# firefly_xiao.net
KiCad netlist of a schematic drawn in EasyEDA Pro
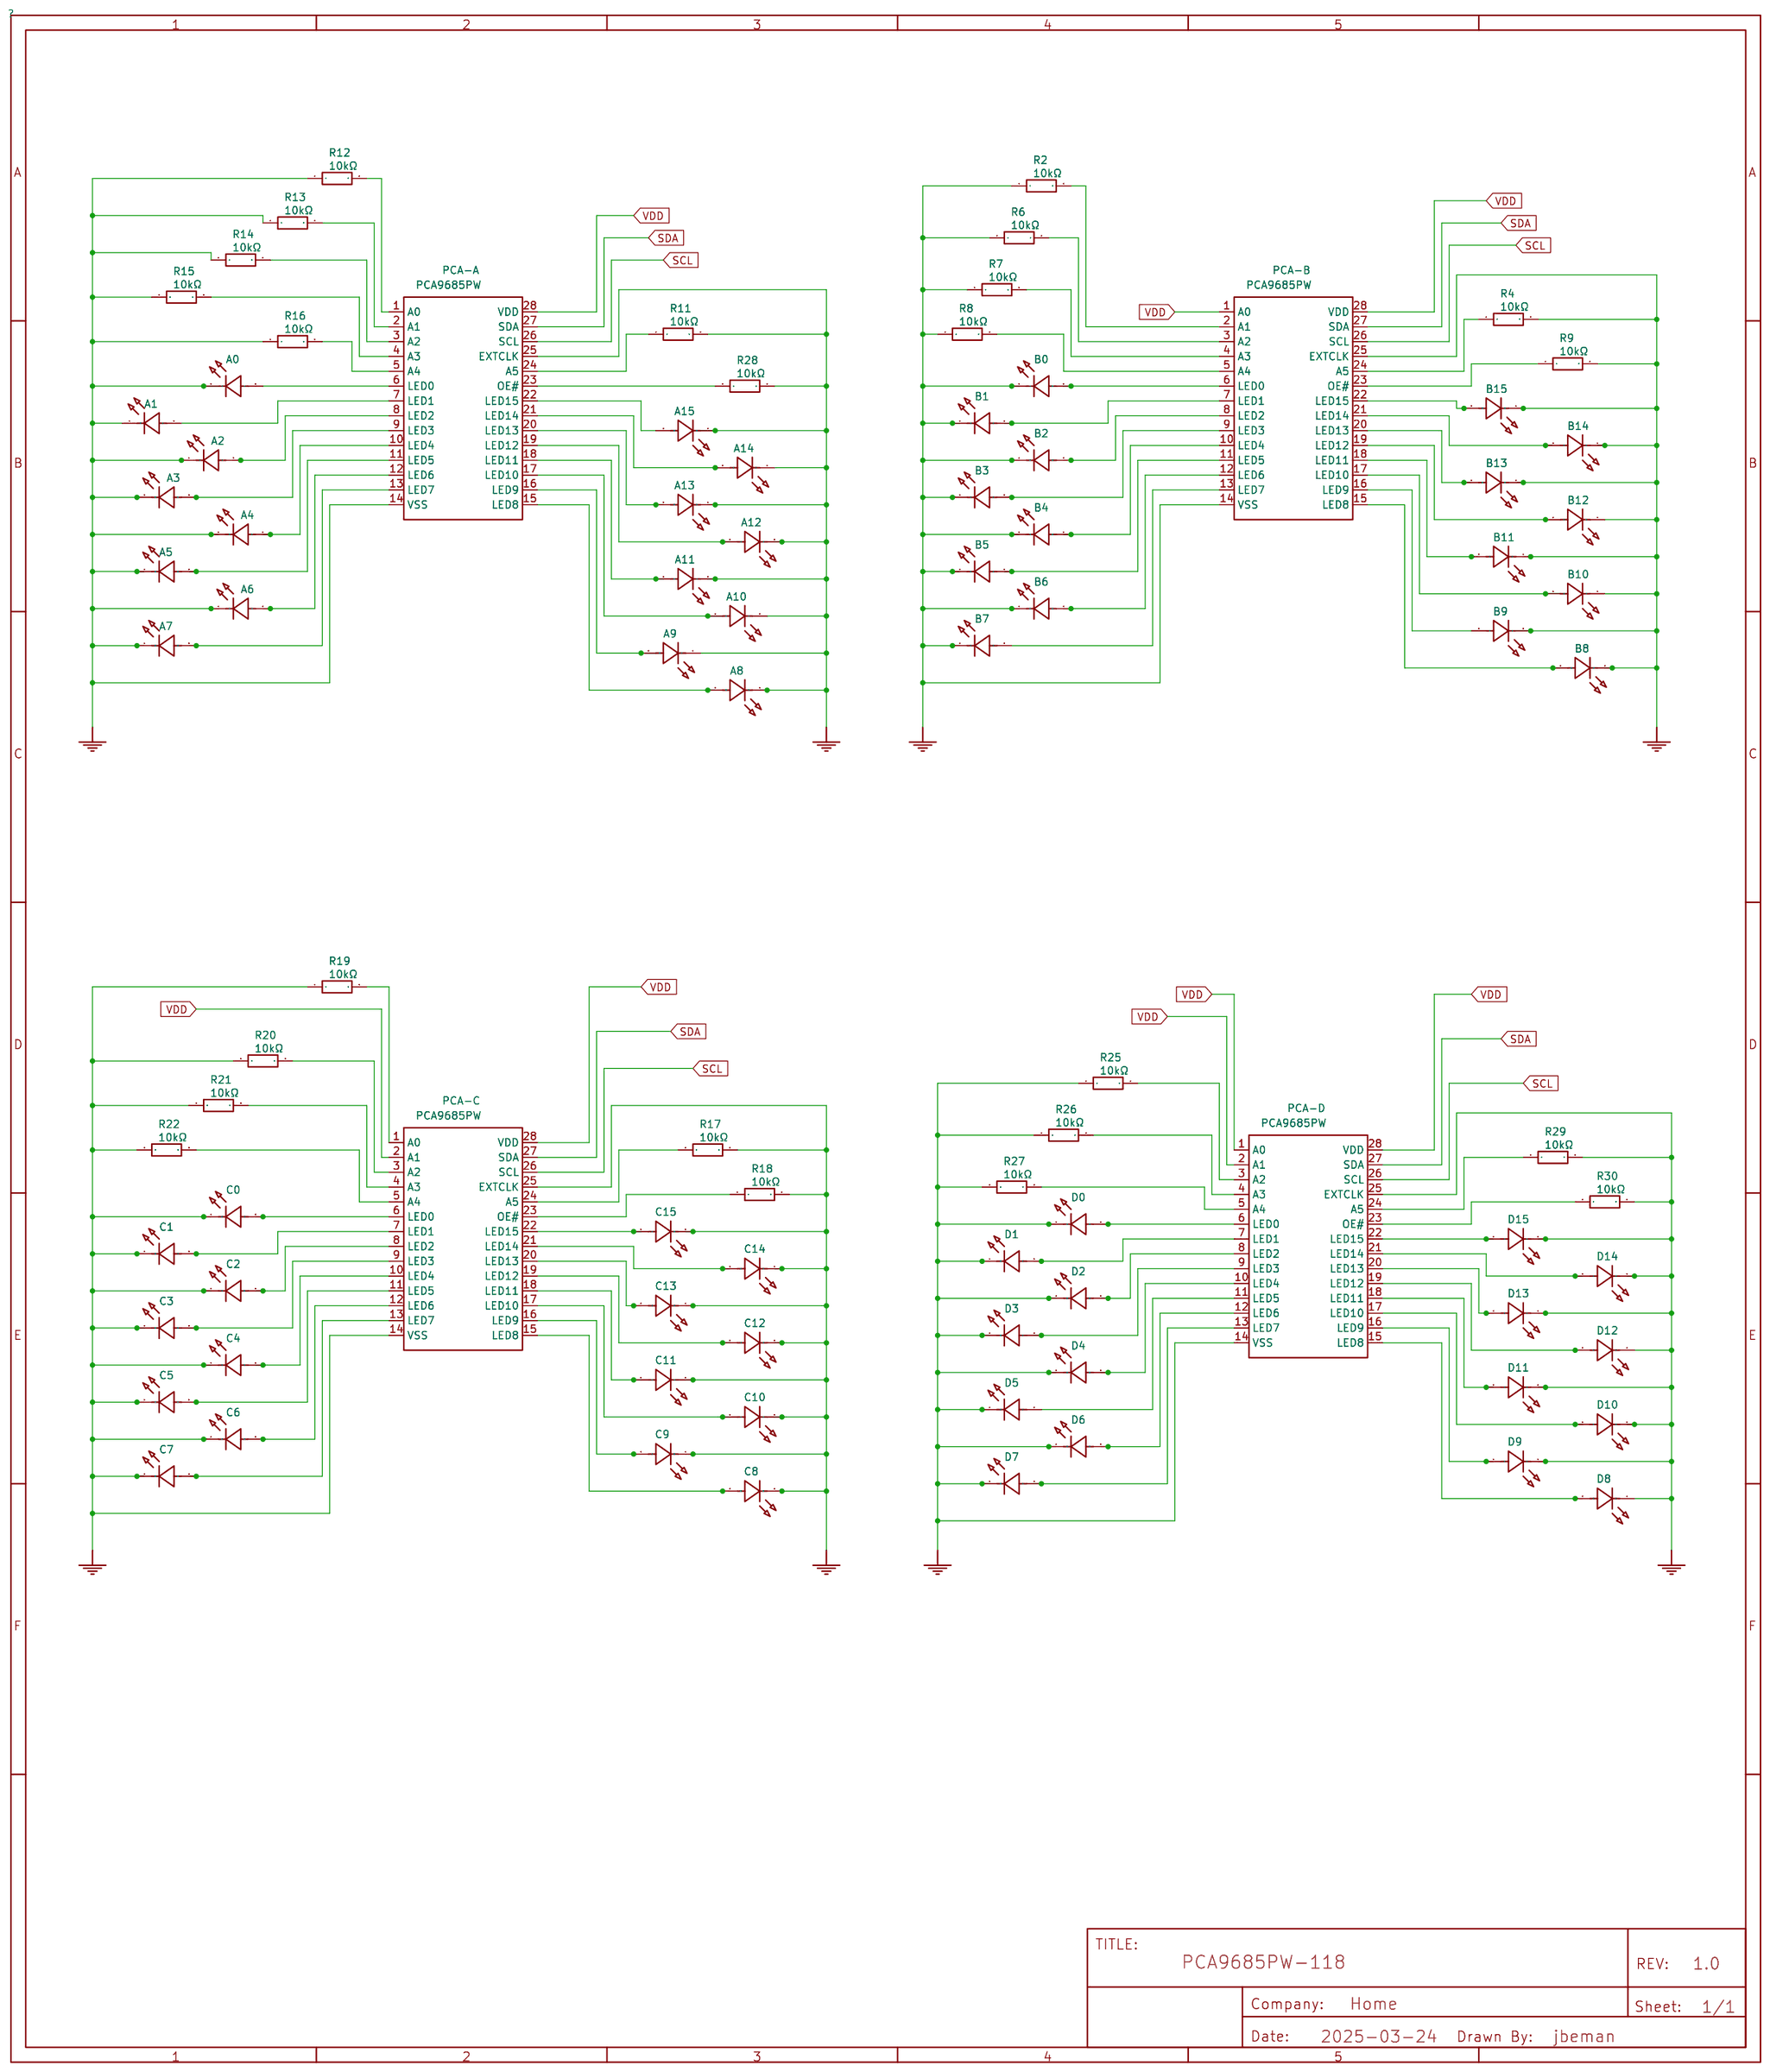
[diagram p0: PCA]
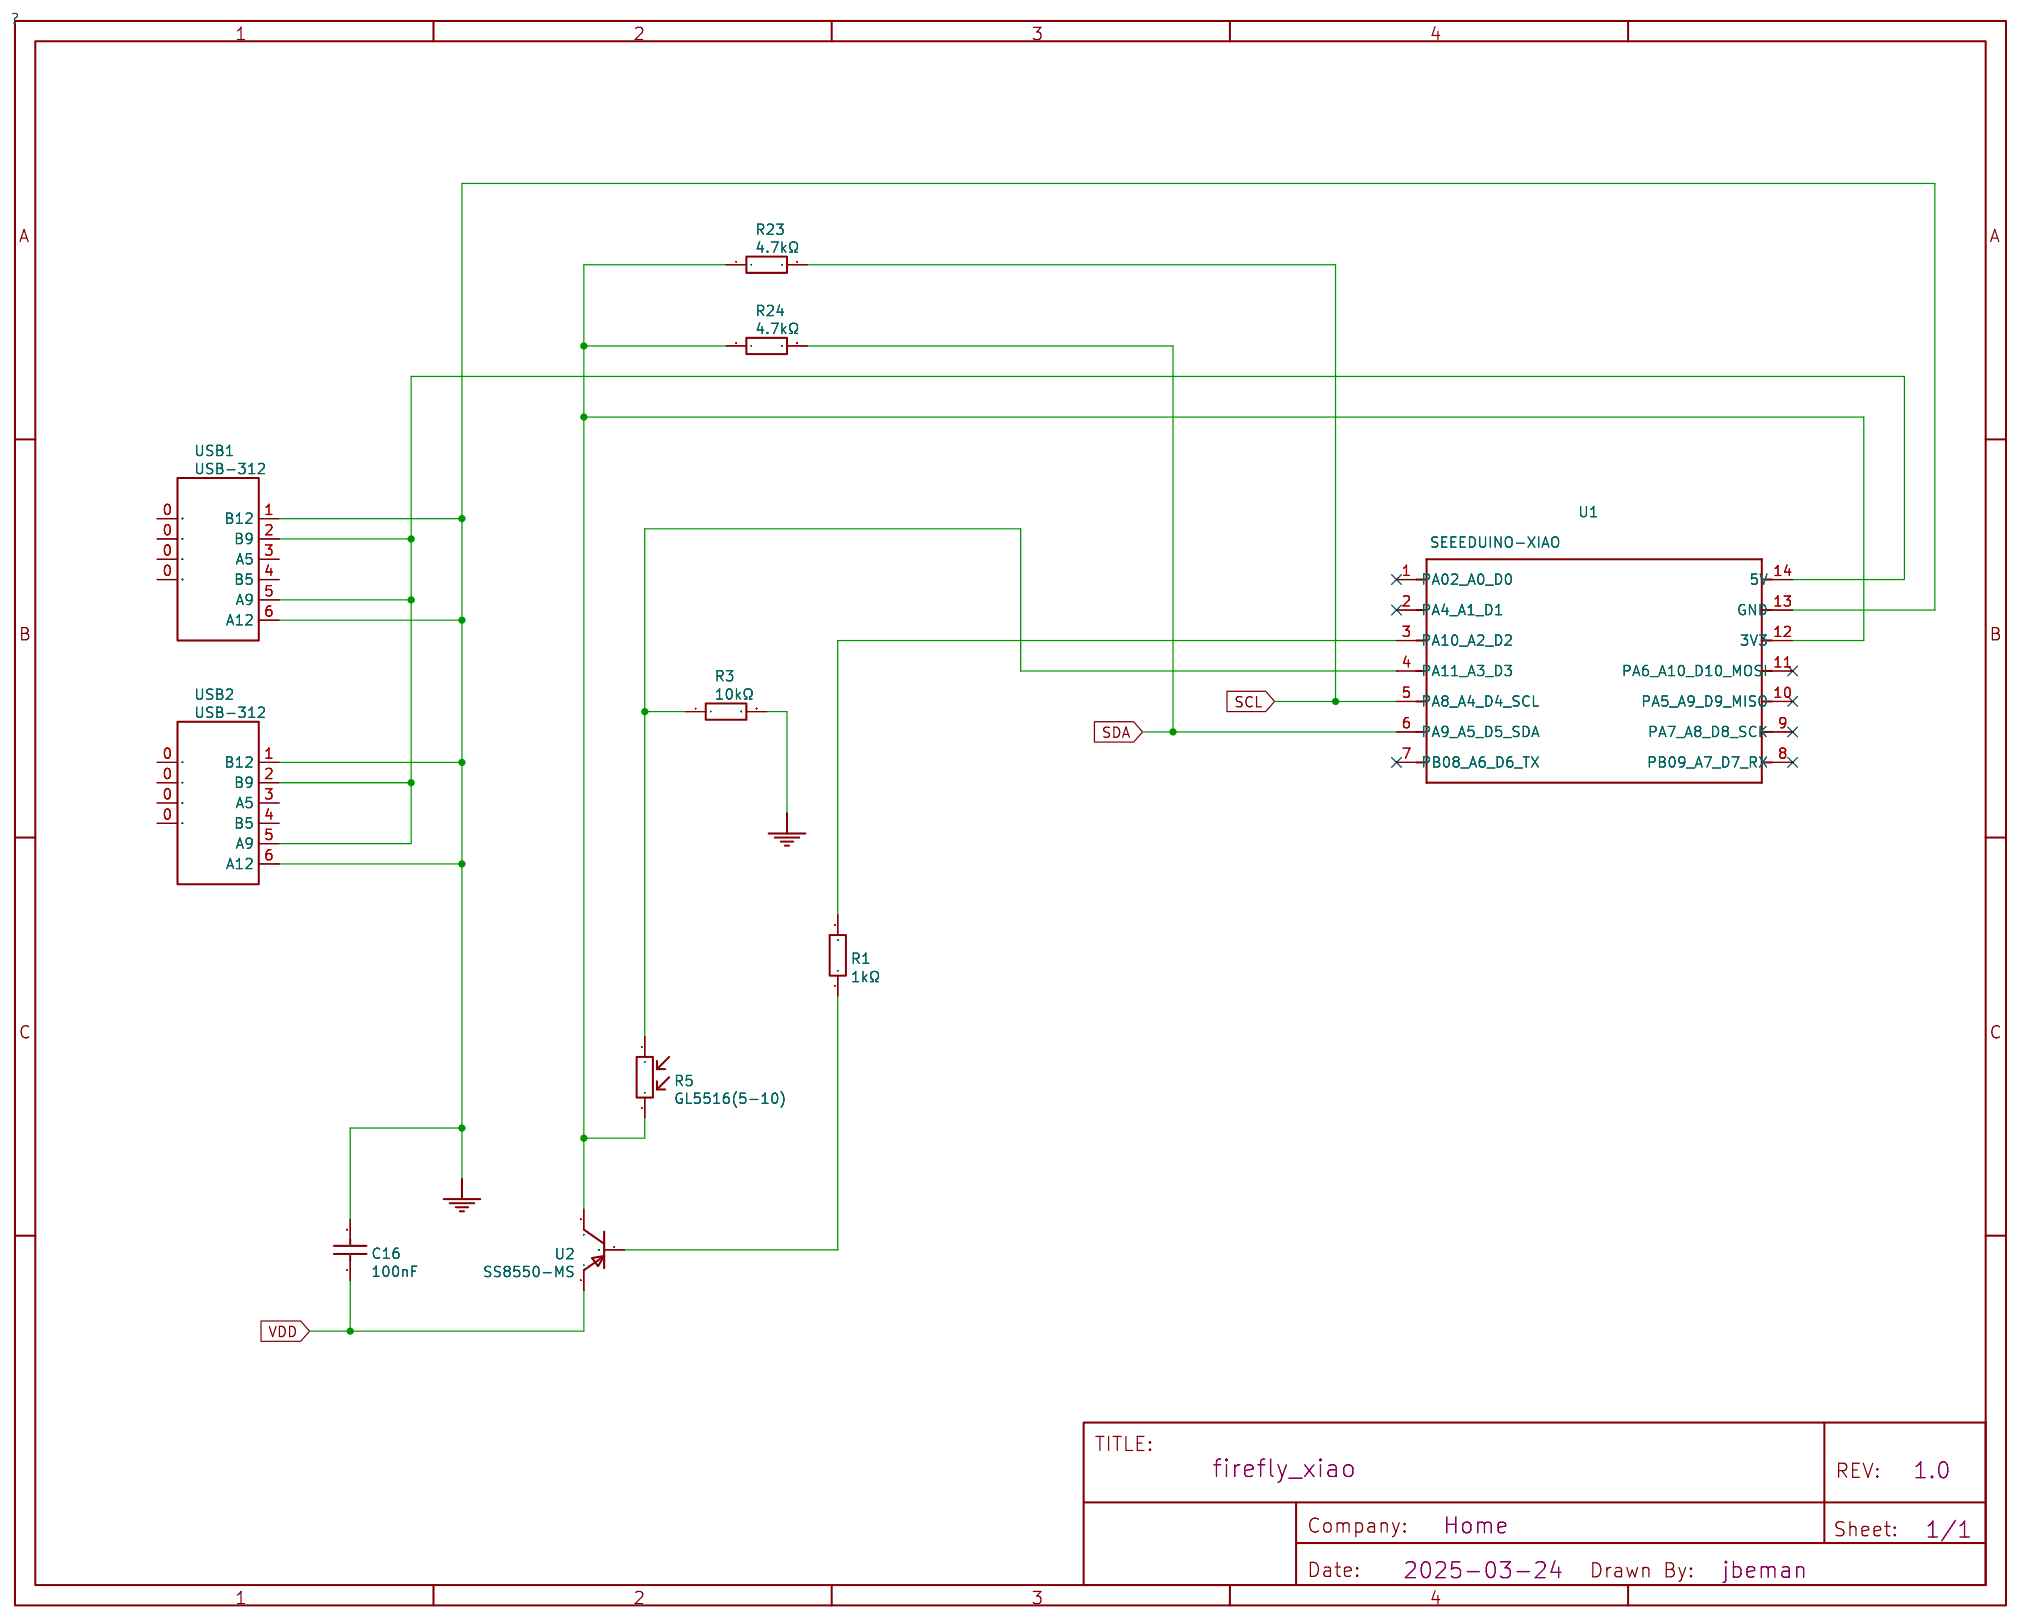
[diagram p1: Controller]

(export (version "E")
  (design (tool "Eeschema 10.0.6"))
  (components
    (comp (ref "A0")
      (value "XL-2012WWC")
      (footprint "easyedapro:LED0805-RD_WHITE")
      (fields (field (name "Manufacturer") "XINGLIGHT(成兴光)") (field (name "Contributor") "lcsc"))
      (libsource (lib "easyedapro") (part "XL-2012WWC"))
    )
    (comp (ref "A1")
      (value "XL-2012WWC")
      (footprint "easyedapro:LED0805-RD_WHITE")
      (fields (field (name "Manufacturer") "XINGLIGHT(成兴光)") (field (name "Contributor") "lcsc"))
      (libsource (lib "easyedapro") (part "XL-2012WWC"))
    )
    (comp (ref "A2")
      (value "XL-2012WWC")
      (footprint "easyedapro:LED0805-RD_WHITE")
      (fields (field (name "Manufacturer") "XINGLIGHT(成兴光)") (field (name "Contributor") "lcsc"))
      (libsource (lib "easyedapro") (part "XL-2012WWC"))
    )
    (comp (ref "A3")
      (value "XL-2012WWC")
      (footprint "easyedapro:LED0805-RD_WHITE")
      (fields (field (name "Manufacturer") "XINGLIGHT(成兴光)") (field (name "Contributor") "lcsc"))
      (libsource (lib "easyedapro") (part "XL-2012WWC"))
    )
    (comp (ref "A4")
      (value "XL-2012WWC")
      (footprint "easyedapro:LED0805-RD_WHITE")
      (fields (field (name "Manufacturer") "XINGLIGHT(成兴光)") (field (name "Contributor") "lcsc"))
      (libsource (lib "easyedapro") (part "XL-2012WWC"))
    )
    (comp (ref "A5")
      (value "XL-2012WWC")
      (footprint "easyedapro:LED0805-RD_WHITE")
      (fields (field (name "Manufacturer") "XINGLIGHT(成兴光)") (field (name "Contributor") "lcsc"))
      (libsource (lib "easyedapro") (part "XL-2012WWC"))
    )
    (comp (ref "A6")
      (value "XL-2012WWC")
      (footprint "easyedapro:LED0805-RD_WHITE")
      (fields (field (name "Manufacturer") "XINGLIGHT(成兴光)") (field (name "Contributor") "lcsc"))
      (libsource (lib "easyedapro") (part "XL-2012WWC"))
    )
    (comp (ref "A7")
      (value "XL-2012WWC")
      (footprint "easyedapro:LED0805-RD_WHITE")
      (fields (field (name "Manufacturer") "XINGLIGHT(成兴光)") (field (name "Contributor") "lcsc"))
      (libsource (lib "easyedapro") (part "XL-2012WWC"))
    )
    (comp (ref "A8")
      (value "XL-2012WWC")
      (footprint "easyedapro:LED0805-RD_WHITE")
      (fields (field (name "Manufacturer") "XINGLIGHT(成兴光)") (field (name "Contributor") "lcsc"))
      (libsource (lib "easyedapro") (part "XL-2012WWC"))
    )
    (comp (ref "A9")
      (value "XL-2012WWC")
      (footprint "easyedapro:LED0805-RD_WHITE")
      (fields (field (name "Manufacturer") "XINGLIGHT(成兴光)") (field (name "Contributor") "lcsc"))
      (libsource (lib "easyedapro") (part "XL-2012WWC"))
    )
    (comp (ref "A10")
      (value "XL-2012WWC")
      (footprint "easyedapro:LED0805-RD_WHITE")
      (fields (field (name "Manufacturer") "XINGLIGHT(成兴光)") (field (name "Contributor") "lcsc"))
      (libsource (lib "easyedapro") (part "XL-2012WWC"))
    )
    (comp (ref "A11")
      (value "XL-2012WWC")
      (footprint "easyedapro:LED0805-RD_WHITE")
      (fields (field (name "Manufacturer") "XINGLIGHT(成兴光)") (field (name "Contributor") "lcsc"))
      (libsource (lib "easyedapro") (part "XL-2012WWC"))
    )
    (comp (ref "A12")
      (value "XL-2012WWC")
      (footprint "easyedapro:LED0805-RD_WHITE")
      (fields (field (name "Manufacturer") "XINGLIGHT(成兴光)") (field (name "Contributor") "lcsc"))
      (libsource (lib "easyedapro") (part "XL-2012WWC"))
    )
    (comp (ref "A13")
      (value "XL-2012WWC")
      (footprint "easyedapro:LED0805-RD_WHITE")
      (fields (field (name "Manufacturer") "XINGLIGHT(成兴光)") (field (name "Contributor") "lcsc"))
      (libsource (lib "easyedapro") (part "XL-2012WWC"))
    )
    (comp (ref "A14")
      (value "XL-2012WWC")
      (footprint "easyedapro:LED0805-RD_WHITE")
      (fields (field (name "Manufacturer") "XINGLIGHT(成兴光)") (field (name "Contributor") "lcsc"))
      (libsource (lib "easyedapro") (part "XL-2012WWC"))
    )
    (comp (ref "A15")
      (value "XL-2012WWC")
      (footprint "easyedapro:LED0805-RD_WHITE")
      (fields (field (name "Manufacturer") "XINGLIGHT(成兴光)") (field (name "Contributor") "lcsc"))
      (libsource (lib "easyedapro") (part "XL-2012WWC"))
    )
    (comp (ref "B0")
      (value "XL-2012WWC")
      (footprint "easyedapro:LED0805-RD_WHITE")
      (fields (field (name "Manufacturer") "XINGLIGHT(成兴光)") (field (name "Contributor") "lcsc"))
      (libsource (lib "easyedapro") (part "XL-2012WWC"))
    )
    (comp (ref "B1")
      (value "XL-2012WWC")
      (footprint "easyedapro:LED0805-RD_WHITE")
      (fields (field (name "Manufacturer") "XINGLIGHT(成兴光)") (field (name "Contributor") "lcsc"))
      (libsource (lib "easyedapro") (part "XL-2012WWC"))
    )
    (comp (ref "B2")
      (value "XL-2012WWC")
      (footprint "easyedapro:LED0805-RD_WHITE")
      (fields (field (name "Manufacturer") "XINGLIGHT(成兴光)") (field (name "Contributor") "lcsc"))
      (libsource (lib "easyedapro") (part "XL-2012WWC"))
    )
    (comp (ref "B3")
      (value "XL-2012WWC")
      (footprint "easyedapro:LED0805-RD_WHITE")
      (fields (field (name "Manufacturer") "XINGLIGHT(成兴光)") (field (name "Contributor") "lcsc"))
      (libsource (lib "easyedapro") (part "XL-2012WWC"))
    )
    (comp (ref "B4")
      (value "XL-2012WWC")
      (footprint "easyedapro:LED0805-RD_WHITE")
      (fields (field (name "Manufacturer") "XINGLIGHT(成兴光)") (field (name "Contributor") "lcsc"))
      (libsource (lib "easyedapro") (part "XL-2012WWC"))
    )
    (comp (ref "B5")
      (value "XL-2012WWC")
      (footprint "easyedapro:LED0805-RD_WHITE")
      (fields (field (name "Manufacturer") "XINGLIGHT(成兴光)") (field (name "Contributor") "lcsc"))
      (libsource (lib "easyedapro") (part "XL-2012WWC"))
    )
    (comp (ref "B6")
      (value "XL-2012WWC")
      (footprint "easyedapro:LED0805-RD_WHITE")
      (fields (field (name "Manufacturer") "XINGLIGHT(成兴光)") (field (name "Contributor") "lcsc"))
      (libsource (lib "easyedapro") (part "XL-2012WWC"))
    )
    (comp (ref "B7")
      (value "XL-2012WWC")
      (footprint "easyedapro:LED0805-RD_WHITE")
      (fields (field (name "Manufacturer") "XINGLIGHT(成兴光)") (field (name "Contributor") "lcsc"))
      (libsource (lib "easyedapro") (part "XL-2012WWC"))
    )
    (comp (ref "B8")
      (value "XL-2012WWC")
      (footprint "easyedapro:LED0805-RD_WHITE")
      (fields (field (name "Manufacturer") "XINGLIGHT(成兴光)") (field (name "Contributor") "lcsc"))
      (libsource (lib "easyedapro") (part "XL-2012WWC"))
    )
    (comp (ref "B9")
      (value "XL-2012WWC")
      (footprint "easyedapro:LED0805-RD_WHITE")
      (fields (field (name "Manufacturer") "XINGLIGHT(成兴光)") (field (name "Contributor") "lcsc"))
      (libsource (lib "easyedapro") (part "XL-2012WWC"))
    )
    (comp (ref "B10")
      (value "XL-2012WWC")
      (footprint "easyedapro:LED0805-RD_WHITE")
      (fields (field (name "Manufacturer") "XINGLIGHT(成兴光)") (field (name "Contributor") "lcsc"))
      (libsource (lib "easyedapro") (part "XL-2012WWC"))
    )
    (comp (ref "B11")
      (value "XL-2012WWC")
      (footprint "easyedapro:LED0805-RD_WHITE")
      (fields (field (name "Manufacturer") "XINGLIGHT(成兴光)") (field (name "Contributor") "lcsc"))
      (libsource (lib "easyedapro") (part "XL-2012WWC"))
    )
    (comp (ref "B12")
      (value "XL-2012WWC")
      (footprint "easyedapro:LED0805-RD_WHITE")
      (fields (field (name "Manufacturer") "XINGLIGHT(成兴光)") (field (name "Contributor") "lcsc"))
      (libsource (lib "easyedapro") (part "XL-2012WWC"))
    )
    (comp (ref "B13")
      (value "XL-2012WWC")
      (footprint "easyedapro:LED0805-RD_WHITE")
      (fields (field (name "Manufacturer") "XINGLIGHT(成兴光)") (field (name "Contributor") "lcsc"))
      (libsource (lib "easyedapro") (part "XL-2012WWC"))
    )
    (comp (ref "B14")
      (value "XL-2012WWC")
      (footprint "easyedapro:LED0805-RD_WHITE")
      (fields (field (name "Manufacturer") "XINGLIGHT(成兴光)") (field (name "Contributor") "lcsc"))
      (libsource (lib "easyedapro") (part "XL-2012WWC"))
    )
    (comp (ref "B15")
      (value "XL-2012WWC")
      (footprint "easyedapro:LED0805-RD_WHITE")
      (fields (field (name "Manufacturer") "XINGLIGHT(成兴光)") (field (name "Contributor") "lcsc"))
      (libsource (lib "easyedapro") (part "XL-2012WWC"))
    )
    (comp (ref "C0")
      (value "XL-2012WWC")
      (footprint "easyedapro:LED0805-RD_WHITE")
      (fields (field (name "Manufacturer") "XINGLIGHT(成兴光)") (field (name "Contributor") "lcsc"))
      (libsource (lib "easyedapro") (part "XL-2012WWC"))
    )
    (comp (ref "C1")
      (value "XL-2012WWC")
      (footprint "easyedapro:LED0805-RD_WHITE")
      (fields (field (name "Manufacturer") "XINGLIGHT(成兴光)") (field (name "Contributor") "lcsc"))
      (libsource (lib "easyedapro") (part "XL-2012WWC"))
    )
    (comp (ref "C2")
      (value "XL-2012WWC")
      (footprint "easyedapro:LED0805-RD_WHITE")
      (fields (field (name "Manufacturer") "XINGLIGHT(成兴光)") (field (name "Contributor") "lcsc"))
      (libsource (lib "easyedapro") (part "XL-2012WWC"))
    )
    (comp (ref "C3")
      (value "XL-2012WWC")
      (footprint "easyedapro:LED0805-RD_WHITE")
      (fields (field (name "Manufacturer") "XINGLIGHT(成兴光)") (field (name "Contributor") "lcsc"))
      (libsource (lib "easyedapro") (part "XL-2012WWC"))
    )
    (comp (ref "C4")
      (value "XL-2012WWC")
      (footprint "easyedapro:LED0805-RD_WHITE")
      (fields (field (name "Manufacturer") "XINGLIGHT(成兴光)") (field (name "Contributor") "lcsc"))
      (libsource (lib "easyedapro") (part "XL-2012WWC"))
    )
    (comp (ref "C5")
      (value "XL-2012WWC")
      (footprint "easyedapro:LED0805-RD_WHITE")
      (fields (field (name "Manufacturer") "XINGLIGHT(成兴光)") (field (name "Contributor") "lcsc"))
      (libsource (lib "easyedapro") (part "XL-2012WWC"))
    )
    (comp (ref "C6")
      (value "XL-2012WWC")
      (footprint "easyedapro:LED0805-RD_WHITE")
      (fields (field (name "Manufacturer") "XINGLIGHT(成兴光)") (field (name "Contributor") "lcsc"))
      (libsource (lib "easyedapro") (part "XL-2012WWC"))
    )
    (comp (ref "C7")
      (value "XL-2012WWC")
      (footprint "easyedapro:LED0805-RD_WHITE")
      (fields (field (name "Manufacturer") "XINGLIGHT(成兴光)") (field (name "Contributor") "lcsc"))
      (libsource (lib "easyedapro") (part "XL-2012WWC"))
    )
    (comp (ref "C8")
      (value "XL-2012WWC")
      (footprint "easyedapro:LED0805-RD_WHITE")
      (fields (field (name "Manufacturer") "XINGLIGHT(成兴光)") (field (name "Contributor") "lcsc"))
      (libsource (lib "easyedapro") (part "XL-2012WWC"))
    )
    (comp (ref "C9")
      (value "XL-2012WWC")
      (footprint "easyedapro:LED0805-RD_WHITE")
      (fields (field (name "Manufacturer") "XINGLIGHT(成兴光)") (field (name "Contributor") "lcsc"))
      (libsource (lib "easyedapro") (part "XL-2012WWC"))
    )
    (comp (ref "C10")
      (value "XL-2012WWC")
      (footprint "easyedapro:LED0805-RD_WHITE")
      (fields (field (name "Manufacturer") "XINGLIGHT(成兴光)") (field (name "Contributor") "lcsc"))
      (libsource (lib "easyedapro") (part "XL-2012WWC"))
    )
    (comp (ref "C11")
      (value "XL-2012WWC")
      (footprint "easyedapro:LED0805-RD_WHITE")
      (fields (field (name "Manufacturer") "XINGLIGHT(成兴光)") (field (name "Contributor") "lcsc"))
      (libsource (lib "easyedapro") (part "XL-2012WWC"))
    )
    (comp (ref "C12")
      (value "XL-2012WWC")
      (footprint "easyedapro:LED0805-RD_WHITE")
      (fields (field (name "Manufacturer") "XINGLIGHT(成兴光)") (field (name "Contributor") "lcsc"))
      (libsource (lib "easyedapro") (part "XL-2012WWC"))
    )
    (comp (ref "C13")
      (value "XL-2012WWC")
      (footprint "easyedapro:LED0805-RD_WHITE")
      (fields (field (name "Manufacturer") "XINGLIGHT(成兴光)") (field (name "Contributor") "lcsc"))
      (libsource (lib "easyedapro") (part "XL-2012WWC"))
    )
    (comp (ref "C14")
      (value "XL-2012WWC")
      (footprint "easyedapro:LED0805-RD_WHITE")
      (fields (field (name "Manufacturer") "XINGLIGHT(成兴光)") (field (name "Contributor") "lcsc"))
      (libsource (lib "easyedapro") (part "XL-2012WWC"))
    )
    (comp (ref "C15")
      (value "XL-2012WWC")
      (footprint "easyedapro:LED0805-RD_WHITE")
      (fields (field (name "Manufacturer") "XINGLIGHT(成兴光)") (field (name "Contributor") "lcsc"))
      (libsource (lib "easyedapro") (part "XL-2012WWC"))
    )
    (comp (ref "D0")
      (value "XL-2012WWC")
      (footprint "easyedapro:LED0805-RD_WHITE")
      (fields (field (name "Manufacturer") "XINGLIGHT(成兴光)") (field (name "Contributor") "lcsc"))
      (libsource (lib "easyedapro") (part "XL-2012WWC"))
    )
    (comp (ref "D1")
      (value "XL-2012WWC")
      (footprint "easyedapro:LED0805-RD_WHITE")
      (fields (field (name "Manufacturer") "XINGLIGHT(成兴光)") (field (name "Contributor") "lcsc"))
      (libsource (lib "easyedapro") (part "XL-2012WWC"))
    )
    (comp (ref "D2")
      (value "XL-2012WWC")
      (footprint "easyedapro:LED0805-RD_WHITE")
      (fields (field (name "Manufacturer") "XINGLIGHT(成兴光)") (field (name "Contributor") "lcsc"))
      (libsource (lib "easyedapro") (part "XL-2012WWC"))
    )
    (comp (ref "D3")
      (value "XL-2012WWC")
      (footprint "easyedapro:LED0805-RD_WHITE")
      (fields (field (name "Manufacturer") "XINGLIGHT(成兴光)") (field (name "Contributor") "lcsc"))
      (libsource (lib "easyedapro") (part "XL-2012WWC"))
    )
    (comp (ref "D4")
      (value "XL-2012WWC")
      (footprint "easyedapro:LED0805-RD_WHITE")
      (fields (field (name "Manufacturer") "XINGLIGHT(成兴光)") (field (name "Contributor") "lcsc"))
      (libsource (lib "easyedapro") (part "XL-2012WWC"))
    )
    (comp (ref "D5")
      (value "XL-2012WWC")
      (footprint "easyedapro:LED0805-RD_WHITE")
      (fields (field (name "Manufacturer") "XINGLIGHT(成兴光)") (field (name "Contributor") "lcsc"))
      (libsource (lib "easyedapro") (part "XL-2012WWC"))
    )
    (comp (ref "D6")
      (value "XL-2012WWC")
      (footprint "easyedapro:LED0805-RD_WHITE")
      (fields (field (name "Manufacturer") "XINGLIGHT(成兴光)") (field (name "Contributor") "lcsc"))
      (libsource (lib "easyedapro") (part "XL-2012WWC"))
    )
    (comp (ref "D7")
      (value "XL-2012WWC")
      (footprint "easyedapro:LED0805-RD_WHITE")
      (fields (field (name "Manufacturer") "XINGLIGHT(成兴光)") (field (name "Contributor") "lcsc"))
      (libsource (lib "easyedapro") (part "XL-2012WWC"))
    )
    (comp (ref "D8")
      (value "XL-2012WWC")
      (footprint "easyedapro:LED0805-RD_WHITE")
      (fields (field (name "Manufacturer") "XINGLIGHT(成兴光)") (field (name "Contributor") "lcsc"))
      (libsource (lib "easyedapro") (part "XL-2012WWC"))
    )
    (comp (ref "D9")
      (value "XL-2012WWC")
      (footprint "easyedapro:LED0805-RD_WHITE")
      (fields (field (name "Manufacturer") "XINGLIGHT(成兴光)") (field (name "Contributor") "lcsc"))
      (libsource (lib "easyedapro") (part "XL-2012WWC"))
    )
    (comp (ref "D10")
      (value "XL-2012WWC")
      (footprint "easyedapro:LED0805-RD_WHITE")
      (fields (field (name "Manufacturer") "XINGLIGHT(成兴光)") (field (name "Contributor") "lcsc"))
      (libsource (lib "easyedapro") (part "XL-2012WWC"))
    )
    (comp (ref "D11")
      (value "XL-2012WWC")
      (footprint "easyedapro:LED0805-RD_WHITE")
      (fields (field (name "Manufacturer") "XINGLIGHT(成兴光)") (field (name "Contributor") "lcsc"))
      (libsource (lib "easyedapro") (part "XL-2012WWC"))
    )
    (comp (ref "D12")
      (value "XL-2012WWC")
      (footprint "easyedapro:LED0805-RD_WHITE")
      (fields (field (name "Manufacturer") "XINGLIGHT(成兴光)") (field (name "Contributor") "lcsc"))
      (libsource (lib "easyedapro") (part "XL-2012WWC"))
    )
    (comp (ref "D13")
      (value "XL-2012WWC")
      (footprint "easyedapro:LED0805-RD_WHITE")
      (fields (field (name "Manufacturer") "XINGLIGHT(成兴光)") (field (name "Contributor") "lcsc"))
      (libsource (lib "easyedapro") (part "XL-2012WWC"))
    )
    (comp (ref "D14")
      (value "XL-2012WWC")
      (footprint "easyedapro:LED0805-RD_WHITE")
      (fields (field (name "Manufacturer") "XINGLIGHT(成兴光)") (field (name "Contributor") "lcsc"))
      (libsource (lib "easyedapro") (part "XL-2012WWC"))
    )
    (comp (ref "D15")
      (value "XL-2012WWC")
      (footprint "easyedapro:LED0805-RD_WHITE")
      (fields (field (name "Manufacturer") "XINGLIGHT(成兴光)") (field (name "Contributor") "lcsc"))
      (libsource (lib "easyedapro") (part "XL-2012WWC"))
    )
    (comp (ref "PCA-A")
      (value "PCA9685PW")
      (footprint "easyedapro:TSSOP-28_L9.7-W4.4-P0.65-LS6.4-TL")
      (fields
        (field (name "Manufacturer Part") "PCA9685PW,118")
        (field (name "Manufacturer") "NXP(恩智浦)")
        (field (name "Contributor") "LCSC")
      )
      (libsource (lib "easyedapro") (part "PCA9685PW"))
    )
    (comp (ref "PCA-B")
      (value "PCA9685PW")
      (footprint "easyedapro:TSSOP-28_L9.7-W4.4-P0.65-LS6.4-TL")
      (fields
        (field (name "Manufacturer Part") "PCA9685PW,118")
        (field (name "Manufacturer") "NXP(恩智浦)")
        (field (name "Contributor") "LCSC")
      )
      (libsource (lib "easyedapro") (part "PCA9685PW"))
    )
    (comp (ref "PCA-C")
      (value "PCA9685PW")
      (footprint "easyedapro:TSSOP-28_L9.7-W4.4-P0.65-LS6.4-TL")
      (fields
        (field (name "Manufacturer Part") "PCA9685PW,118")
        (field (name "Manufacturer") "NXP(恩智浦)")
        (field (name "Contributor") "LCSC")
      )
      (libsource (lib "easyedapro") (part "PCA9685PW"))
    )
    (comp (ref "PCA-D")
      (value "PCA9685PW")
      (footprint "easyedapro:TSSOP-28_L9.7-W4.4-P0.65-LS6.4-TL")
      (fields
        (field (name "Manufacturer Part") "PCA9685PW,118")
        (field (name "Manufacturer") "NXP(恩智浦)")
        (field (name "Contributor") "LCSC")
      )
      (libsource (lib "easyedapro") (part "PCA9685PW"))
    )
    (comp (ref "R2")
      (value "10kΩ")
      (footprint "easyedapro:R0805")
      (fields
        (field (name "Manufacturer Part") "0805W8F1002T5E")
        (field (name "Manufacturer") "UNI-ROYAL(厚声)")
      )
      (libsource (lib "easyedapro") (part "10kΩ"))
    )
    (comp (ref "R4")
      (value "10kΩ")
      (footprint "easyedapro:R0805")
      (fields
        (field (name "Manufacturer Part") "0805W8F1002T5E")
        (field (name "Manufacturer") "UNI-ROYAL(厚声)")
      )
      (libsource (lib "easyedapro") (part "10kΩ"))
    )
    (comp (ref "R6")
      (value "10kΩ")
      (footprint "easyedapro:R0805")
      (fields
        (field (name "Manufacturer Part") "0805W8F1002T5E")
        (field (name "Manufacturer") "UNI-ROYAL(厚声)")
      )
      (libsource (lib "easyedapro") (part "10kΩ"))
    )
    (comp (ref "R7")
      (value "10kΩ")
      (footprint "easyedapro:R0805")
      (fields
        (field (name "Manufacturer Part") "0805W8F1002T5E")
        (field (name "Manufacturer") "UNI-ROYAL(厚声)")
      )
      (libsource (lib "easyedapro") (part "10kΩ"))
    )
    (comp (ref "R8")
      (value "10kΩ")
      (footprint "easyedapro:R0805")
      (fields
        (field (name "Manufacturer Part") "0805W8F1002T5E")
        (field (name "Manufacturer") "UNI-ROYAL(厚声)")
      )
      (libsource (lib "easyedapro") (part "10kΩ"))
    )
    (comp (ref "R9")
      (value "10kΩ")
      (footprint "easyedapro:R0805")
      (fields
        (field (name "Manufacturer Part") "0805W8F1002T5E")
        (field (name "Manufacturer") "UNI-ROYAL(厚声)")
      )
      (libsource (lib "easyedapro") (part "10kΩ"))
    )
    (comp (ref "R11")
      (value "10kΩ")
      (footprint "easyedapro:R0805")
      (fields
        (field (name "Manufacturer Part") "0805W8F1002T5E")
        (field (name "Manufacturer") "UNI-ROYAL(厚声)")
      )
      (libsource (lib "easyedapro") (part "10kΩ"))
    )
    (comp (ref "R12")
      (value "10kΩ")
      (footprint "easyedapro:R0805")
      (fields
        (field (name "Manufacturer Part") "0805W8F1002T5E")
        (field (name "Manufacturer") "UNI-ROYAL(厚声)")
      )
      (libsource (lib "easyedapro") (part "10kΩ"))
    )
    (comp (ref "R13")
      (value "10kΩ")
      (footprint "easyedapro:R0805")
      (fields
        (field (name "Manufacturer Part") "0805W8F1002T5E")
        (field (name "Manufacturer") "UNI-ROYAL(厚声)")
      )
      (libsource (lib "easyedapro") (part "10kΩ"))
    )
    (comp (ref "R14")
      (value "10kΩ")
      (footprint "easyedapro:R0805")
      (fields
        (field (name "Manufacturer Part") "0805W8F1002T5E")
        (field (name "Manufacturer") "UNI-ROYAL(厚声)")
      )
      (libsource (lib "easyedapro") (part "10kΩ"))
    )
    (comp (ref "R15")
      (value "10kΩ")
      (footprint "easyedapro:R0805")
      (fields
        (field (name "Manufacturer Part") "0805W8F1002T5E")
        (field (name "Manufacturer") "UNI-ROYAL(厚声)")
      )
      (libsource (lib "easyedapro") (part "10kΩ"))
    )
    (comp (ref "R16")
      (value "10kΩ")
      (footprint "easyedapro:R0805")
      (fields
        (field (name "Manufacturer Part") "0805W8F1002T5E")
        (field (name "Manufacturer") "UNI-ROYAL(厚声)")
      )
      (libsource (lib "easyedapro") (part "10kΩ"))
    )
    (comp (ref "R17")
      (value "10kΩ")
      (footprint "easyedapro:R0805")
      (fields
        (field (name "Manufacturer Part") "0805W8F1002T5E")
        (field (name "Manufacturer") "UNI-ROYAL(厚声)")
      )
      (libsource (lib "easyedapro") (part "10kΩ"))
    )
    (comp (ref "R18")
      (value "10kΩ")
      (footprint "easyedapro:R0805")
      (fields
        (field (name "Manufacturer Part") "0805W8F1002T5E")
        (field (name "Manufacturer") "UNI-ROYAL(厚声)")
      )
      (libsource (lib "easyedapro") (part "10kΩ"))
    )
    (comp (ref "R19")
      (value "10kΩ")
      (footprint "easyedapro:R0805")
      (fields
        (field (name "Manufacturer Part") "0805W8F1002T5E")
        (field (name "Manufacturer") "UNI-ROYAL(厚声)")
      )
      (libsource (lib "easyedapro") (part "10kΩ"))
    )
    (comp (ref "R20")
      (value "10kΩ")
      (footprint "easyedapro:R0805")
      (fields
        (field (name "Manufacturer Part") "0805W8F1002T5E")
        (field (name "Manufacturer") "UNI-ROYAL(厚声)")
      )
      (libsource (lib "easyedapro") (part "10kΩ"))
    )
    (comp (ref "R21")
      (value "10kΩ")
      (footprint "easyedapro:R0805")
      (fields
        (field (name "Manufacturer Part") "0805W8F1002T5E")
        (field (name "Manufacturer") "UNI-ROYAL(厚声)")
      )
      (libsource (lib "easyedapro") (part "10kΩ"))
    )
    (comp (ref "R22")
      (value "10kΩ")
      (footprint "easyedapro:R0805")
      (fields
        (field (name "Manufacturer Part") "0805W8F1002T5E")
        (field (name "Manufacturer") "UNI-ROYAL(厚声)")
      )
      (libsource (lib "easyedapro") (part "10kΩ"))
    )
    (comp (ref "R25")
      (value "10kΩ")
      (footprint "easyedapro:R0805")
      (fields
        (field (name "Manufacturer Part") "0805W8F1002T5E")
        (field (name "Manufacturer") "UNI-ROYAL(厚声)")
      )
      (libsource (lib "easyedapro") (part "10kΩ"))
    )
    (comp (ref "R26")
      (value "10kΩ")
      (footprint "easyedapro:R0805")
      (fields
        (field (name "Manufacturer Part") "0805W8F1002T5E")
        (field (name "Manufacturer") "UNI-ROYAL(厚声)")
      )
      (libsource (lib "easyedapro") (part "10kΩ"))
    )
    (comp (ref "R27")
      (value "10kΩ")
      (footprint "easyedapro:R0805")
      (fields
        (field (name "Manufacturer Part") "0805W8F1002T5E")
        (field (name "Manufacturer") "UNI-ROYAL(厚声)")
      )
      (libsource (lib "easyedapro") (part "10kΩ"))
    )
    (comp (ref "R28")
      (value "10kΩ")
      (footprint "easyedapro:R0805")
      (fields
        (field (name "Manufacturer Part") "0805W8F1002T5E")
        (field (name "Manufacturer") "UNI-ROYAL(厚声)")
      )
      (libsource (lib "easyedapro") (part "10kΩ"))
    )
    (comp (ref "R29")
      (value "10kΩ")
      (footprint "easyedapro:R0805")
      (fields
        (field (name "Manufacturer Part") "0805W8F1002T5E")
        (field (name "Manufacturer") "UNI-ROYAL(厚声)")
      )
      (libsource (lib "easyedapro") (part "10kΩ"))
    )
    (comp (ref "R30")
      (value "10kΩ")
      (footprint "easyedapro:R0805")
      (fields
        (field (name "Manufacturer Part") "0805W8F1002T5E")
        (field (name "Manufacturer") "UNI-ROYAL(厚声)")
      )
      (libsource (lib "easyedapro") (part "10kΩ"))
    )
    (comp (ref "C16")
      (value "100nF")
      (footprint "easyedapro:C0805")
      (fields
        (field (name "Manufacturer Part") "CL21B104KCFNNNE")
        (field (name "Manufacturer") "SAMSUNG(三星)")
      )
      (libsource (lib "easyedapro") (part "100nF"))
    )
    (comp (ref "R1")
      (value "1kΩ")
      (footprint "easyedapro:R0805")
      (fields
        (field (name "Manufacturer Part") "0805W8F1001T5E")
        (field (name "Manufacturer") "UNI-ROYAL(厚声)")
      )
      (libsource (lib "easyedapro") (part "1kΩ"))
    )
    (comp (ref "R3")
      (value "10kΩ")
      (footprint "easyedapro:R0805")
      (fields
        (field (name "Manufacturer Part") "0805W8F1002T5E")
        (field (name "Manufacturer") "UNI-ROYAL(厚声)")
      )
      (libsource (lib "easyedapro") (part "10kΩ"))
    )
    (comp (ref "R5")
      (value "GL5516(5-10)")
      (footprint "easyedapro:RES-TH_L5.1-W4.3-P3.40_GL55")
      (fields (field (name "Manufacturer") "JCHL(晶创和立)"))
      (libsource (lib "easyedapro") (part "GL5516(5-10)"))
    )
    (comp (ref "R23")
      (value "4.7kΩ")
      (footprint "easyedapro:R0805")
      (fields
        (field (name "Manufacturer Part") "0805W8F4701T5E")
        (field (name "Manufacturer") "UNI-ROYAL(厚声)")
      )
      (libsource (lib "easyedapro") (part "4.7kΩ"))
    )
    (comp (ref "R24")
      (value "4.7kΩ")
      (footprint "easyedapro:R0805")
      (fields
        (field (name "Manufacturer Part") "0805W8F4701T5E")
        (field (name "Manufacturer") "UNI-ROYAL(厚声)")
      )
      (libsource (lib "easyedapro") (part "4.7kΩ"))
    )
    (comp (ref "U1")
      (value "SEEEDUINO-XIAO")
      (footprint "easyedapro:MOUDLE14P-SMD-2.54-21X17.8MM")
      (fields (field (name "Contributor") "jbeman"))
      (libsource (lib "easyedapro") (part "SEEEDUINO-XIAO"))
    )
    (comp (ref "U2")
      (value "SS8550-MS")
      (footprint "easyedapro:SOT-23-3_L2.9-W1.3-P1.90-LS2.4-BR")
      (fields (field (name "Manufacturer") "MSKSEMI(美森科)") (field (name "Contributor") "lcsc"))
      (libsource (lib "easyedapro") (part "SS8550-MS"))
    )
    (comp (ref "USB1")
      (value "USB-312")
      (footprint "easyedapro:USB-C-SMD_10P-P1.00-L6.8-W8.9")
      (fields
        (field (name "Manufacturer Part") "USB-312-B-SU")
        (field (name "Manufacturer") "HOOYA(皓宇电子)")
        (field (name "Contributor") "LCSC")
      )
      (libsource (lib "easyedapro") (part "USB-312"))
    )
    (comp (ref "USB2")
      (value "USB-312")
      (footprint "easyedapro:USB-C-SMD_10P-P1.00-L6.8-W8.9")
      (fields
        (field (name "Manufacturer Part") "USB-312-B-SU")
        (field (name "Manufacturer") "HOOYA(皓宇电子)")
        (field (name "Contributor") "LCSC")
      )
      (libsource (lib "easyedapro") (part "USB-312"))
    )
  )
  (nets
    (net (code "1") (name "GND") (class "Default")
      (node (ref "A0") (pin "1") (pinfunction "K_1") (pintype "unspecified"))
      (node (ref "A1") (pin "1") (pinfunction "K_1") (pintype "unspecified"))
      (node (ref "A10") (pin "1") (pinfunction "K_1") (pintype "unspecified"))
      (node (ref "A11") (pin "1") (pinfunction "K_1") (pintype "unspecified"))
      (node (ref "A12") (pin "1") (pinfunction "K_1") (pintype "unspecified"))
      (node (ref "A13") (pin "1") (pinfunction "K_1") (pintype "unspecified"))
      (node (ref "A14") (pin "1") (pinfunction "K_1") (pintype "unspecified"))
      (node (ref "A15") (pin "1") (pinfunction "K_1") (pintype "unspecified"))
      (node (ref "A2") (pin "1") (pinfunction "K_1") (pintype "unspecified"))
      (node (ref "A3") (pin "1") (pinfunction "K_1") (pintype "unspecified"))
      (node (ref "A4") (pin "1") (pinfunction "K_1") (pintype "unspecified"))
      (node (ref "A5") (pin "1") (pinfunction "K_1") (pintype "unspecified"))
      (node (ref "A6") (pin "1") (pinfunction "K_1") (pintype "unspecified"))
      (node (ref "A7") (pin "1") (pinfunction "K_1") (pintype "unspecified"))
      (node (ref "A8") (pin "1") (pinfunction "K_1") (pintype "unspecified"))
      (node (ref "A9") (pin "1") (pinfunction "K_1") (pintype "unspecified"))
      (node (ref "B0") (pin "1") (pinfunction "K_1") (pintype "unspecified"))
      (node (ref "B1") (pin "1") (pinfunction "K_1") (pintype "unspecified"))
      (node (ref "B10") (pin "1") (pinfunction "K_1") (pintype "unspecified"))
      (node (ref "B11") (pin "1") (pinfunction "K_1") (pintype "unspecified"))
      (node (ref "B12") (pin "1") (pinfunction "K_1") (pintype "unspecified"))
      (node (ref "B13") (pin "1") (pinfunction "K_1") (pintype "unspecified"))
      (node (ref "B14") (pin "1") (pinfunction "K_1") (pintype "unspecified"))
      (node (ref "B15") (pin "1") (pinfunction "K_1") (pintype "unspecified"))
      (node (ref "B2") (pin "1") (pinfunction "K_1") (pintype "unspecified"))
      (node (ref "B3") (pin "1") (pinfunction "K_1") (pintype "unspecified"))
      (node (ref "B4") (pin "1") (pinfunction "K_1") (pintype "unspecified"))
      (node (ref "B5") (pin "1") (pinfunction "K_1") (pintype "unspecified"))
      (node (ref "B6") (pin "1") (pinfunction "K_1") (pintype "unspecified"))
      (node (ref "B7") (pin "1") (pinfunction "K_1") (pintype "unspecified"))
      (node (ref "B8") (pin "1") (pinfunction "K_1") (pintype "unspecified"))
      (node (ref "B9") (pin "1") (pinfunction "K_1") (pintype "unspecified"))
      (node (ref "C0") (pin "1") (pinfunction "K_1") (pintype "unspecified"))
      (node (ref "C1") (pin "1") (pinfunction "K_1") (pintype "unspecified"))
      (node (ref "C10") (pin "1") (pinfunction "K_1") (pintype "unspecified"))
      (node (ref "C11") (pin "1") (pinfunction "K_1") (pintype "unspecified"))
      (node (ref "C12") (pin "1") (pinfunction "K_1") (pintype "unspecified"))
      (node (ref "C13") (pin "1") (pinfunction "K_1") (pintype "unspecified"))
      (node (ref "C14") (pin "1") (pinfunction "K_1") (pintype "unspecified"))
      (node (ref "C15") (pin "1") (pinfunction "K_1") (pintype "unspecified"))
      (node (ref "C16") (pin "2") (pinfunction "2_2") (pintype "input"))
      (node (ref "C2") (pin "1") (pinfunction "K_1") (pintype "unspecified"))
      (node (ref "C3") (pin "1") (pinfunction "K_1") (pintype "unspecified"))
      (node (ref "C4") (pin "1") (pinfunction "K_1") (pintype "unspecified"))
      (node (ref "C5") (pin "1") (pinfunction "K_1") (pintype "unspecified"))
      (node (ref "C6") (pin "1") (pinfunction "K_1") (pintype "unspecified"))
      (node (ref "C7") (pin "1") (pinfunction "K_1") (pintype "unspecified"))
      (node (ref "C8") (pin "1") (pinfunction "K_1") (pintype "unspecified"))
      (node (ref "C9") (pin "1") (pinfunction "K_1") (pintype "unspecified"))
      (node (ref "D0") (pin "1") (pinfunction "K_1") (pintype "unspecified"))
      (node (ref "D1") (pin "1") (pinfunction "K_1") (pintype "unspecified"))
      (node (ref "D10") (pin "1") (pinfunction "K_1") (pintype "unspecified"))
      (node (ref "D11") (pin "1") (pinfunction "K_1") (pintype "unspecified"))
      (node (ref "D12") (pin "1") (pinfunction "K_1") (pintype "unspecified"))
      (node (ref "D13") (pin "1") (pinfunction "K_1") (pintype "unspecified"))
      (node (ref "D14") (pin "1") (pinfunction "K_1") (pintype "unspecified"))
      (node (ref "D15") (pin "1") (pinfunction "K_1") (pintype "unspecified"))
      (node (ref "D2") (pin "1") (pinfunction "K_1") (pintype "unspecified"))
      (node (ref "D3") (pin "1") (pinfunction "K_1") (pintype "unspecified"))
      (node (ref "D4") (pin "1") (pinfunction "K_1") (pintype "unspecified"))
      (node (ref "D5") (pin "1") (pinfunction "K_1") (pintype "unspecified"))
      (node (ref "D6") (pin "1") (pinfunction "K_1") (pintype "unspecified"))
      (node (ref "D7") (pin "1") (pinfunction "K_1") (pintype "unspecified"))
      (node (ref "D8") (pin "1") (pinfunction "K_1") (pintype "unspecified"))
      (node (ref "D9") (pin "1") (pinfunction "K_1") (pintype "unspecified"))
      (node (ref "PCA-A") (pin "14") (pinfunction "VSS_14") (pintype "unspecified"))
      (node (ref "PCA-A") (pin "25") (pinfunction "EXTCLK_25") (pintype "unspecified"))
      (node (ref "PCA-B") (pin "14") (pinfunction "VSS_14") (pintype "unspecified"))
      (node (ref "PCA-B") (pin "25") (pinfunction "EXTCLK_25") (pintype "unspecified"))
      (node (ref "PCA-C") (pin "14") (pinfunction "VSS_14") (pintype "unspecified"))
      (node (ref "PCA-C") (pin "25") (pinfunction "EXTCLK_25") (pintype "unspecified"))
      (node (ref "PCA-D") (pin "14") (pinfunction "VSS_14") (pintype "unspecified"))
      (node (ref "PCA-D") (pin "25") (pinfunction "EXTCLK_25") (pintype "unspecified"))
      (node (ref "R11") (pin "2") (pinfunction "2_2") (pintype "input"))
      (node (ref "R12") (pin "1") (pinfunction "1_1") (pintype "input"))
      (node (ref "R13") (pin "1") (pinfunction "1_1") (pintype "input"))
      (node (ref "R14") (pin "1") (pinfunction "1_1") (pintype "input"))
      (node (ref "R15") (pin "1") (pinfunction "1_1") (pintype "input"))
      (node (ref "R16") (pin "1") (pinfunction "1_1") (pintype "input"))
      (node (ref "R17") (pin "2") (pinfunction "2_2") (pintype "input"))
      (node (ref "R18") (pin "2") (pinfunction "2_2") (pintype "input"))
      (node (ref "R19") (pin "1") (pinfunction "1_1") (pintype "input"))
      (node (ref "R2") (pin "1") (pinfunction "1_1") (pintype "input"))
      (node (ref "R20") (pin "1") (pinfunction "1_1") (pintype "input"))
      (node (ref "R21") (pin "1") (pinfunction "1_1") (pintype "input"))
      (node (ref "R22") (pin "1") (pinfunction "1_1") (pintype "input"))
      (node (ref "R25") (pin "1") (pinfunction "1_1") (pintype "input"))
      (node (ref "R26") (pin "1") (pinfunction "1_1") (pintype "input"))
      (node (ref "R27") (pin "1") (pinfunction "1_1") (pintype "input"))
      (node (ref "R28") (pin "2") (pinfunction "2_2") (pintype "input"))
      (node (ref "R29") (pin "2") (pinfunction "2_2") (pintype "input"))
      (node (ref "R3") (pin "2") (pinfunction "2_2") (pintype "input"))
      (node (ref "R30") (pin "2") (pinfunction "2_2") (pintype "input"))
      (node (ref "R4") (pin "2") (pinfunction "2_2") (pintype "input"))
      (node (ref "R6") (pin "1") (pinfunction "1_1") (pintype "input"))
      (node (ref "R7") (pin "1") (pinfunction "1_1") (pintype "input"))
      (node (ref "R8") (pin "1") (pinfunction "1_1") (pintype "input"))
      (node (ref "R9") (pin "2") (pinfunction "2_2") (pintype "input"))
      (node (ref "U1") (pin "13") (pinfunction "GND_13") (pintype "bidirectional"))
      (node (ref "USB1") (pin "1") (pinfunction "B12_1") (pintype "unspecified"))
      (node (ref "USB1") (pin "6") (pinfunction "A12_6") (pintype "unspecified"))
      (node (ref "USB2") (pin "1") (pinfunction "B12_1") (pintype "unspecified"))
      (node (ref "USB2") (pin "6") (pinfunction "A12_6") (pintype "unspecified"))
    )
    (net (code "2") (name "Net-(A0-A)") (class "Default")
      (node (ref "A0") (pin "2") (pinfunction "A_2") (pintype "unspecified"))
      (node (ref "PCA-A") (pin "6") (pinfunction "LED0_6") (pintype "unspecified"))
    )
    (net (code "3") (name "Net-(A1-A)") (class "Default")
      (node (ref "A1") (pin "2") (pinfunction "A_2") (pintype "unspecified"))
      (node (ref "PCA-A") (pin "7") (pinfunction "LED1_7") (pintype "unspecified"))
    )
    (net (code "4") (name "Net-(A2-A)") (class "Default")
      (node (ref "A2") (pin "2") (pinfunction "A_2") (pintype "unspecified"))
      (node (ref "PCA-A") (pin "8") (pinfunction "LED2_8") (pintype "unspecified"))
    )
    (net (code "5") (name "Net-(A3-A)") (class "Default")
      (node (ref "A3") (pin "2") (pinfunction "A_2") (pintype "unspecified"))
      (node (ref "PCA-A") (pin "9") (pinfunction "LED3_9") (pintype "unspecified"))
    )
    (net (code "6") (name "Net-(A4-A)") (class "Default")
      (node (ref "A4") (pin "2") (pinfunction "A_2") (pintype "unspecified"))
      (node (ref "PCA-A") (pin "10") (pinfunction "LED4_10") (pintype "unspecified"))
    )
    (net (code "7") (name "Net-(A5-A)") (class "Default")
      (node (ref "A5") (pin "2") (pinfunction "A_2") (pintype "unspecified"))
      (node (ref "PCA-A") (pin "11") (pinfunction "LED5_11") (pintype "unspecified"))
    )
    (net (code "8") (name "Net-(A6-A)") (class "Default")
      (node (ref "A6") (pin "2") (pinfunction "A_2") (pintype "unspecified"))
      (node (ref "PCA-A") (pin "12") (pinfunction "LED6_12") (pintype "unspecified"))
    )
    (net (code "9") (name "Net-(A7-A)") (class "Default")
      (node (ref "A7") (pin "2") (pinfunction "A_2") (pintype "unspecified"))
      (node (ref "PCA-A") (pin "13") (pinfunction "LED7_13") (pintype "unspecified"))
    )
    (net (code "10") (name "Net-(A8-A)") (class "Default")
      (node (ref "A8") (pin "2") (pinfunction "A_2") (pintype "unspecified"))
      (node (ref "PCA-A") (pin "15") (pinfunction "LED8_15") (pintype "unspecified"))
    )
    (net (code "11") (name "Net-(A9-A)") (class "Default")
      (node (ref "A9") (pin "2") (pinfunction "A_2") (pintype "unspecified"))
      (node (ref "PCA-A") (pin "16") (pinfunction "LED9_16") (pintype "unspecified"))
    )
    (net (code "12") (name "Net-(A10-A)") (class "Default")
      (node (ref "A10") (pin "2") (pinfunction "A_2") (pintype "unspecified"))
      (node (ref "PCA-A") (pin "17") (pinfunction "LED10_17") (pintype "unspecified"))
    )
    (net (code "13") (name "Net-(A11-A)") (class "Default")
      (node (ref "A11") (pin "2") (pinfunction "A_2") (pintype "unspecified"))
      (node (ref "PCA-A") (pin "18") (pinfunction "LED11_18") (pintype "unspecified"))
    )
    (net (code "14") (name "Net-(A12-A)") (class "Default")
      (node (ref "A12") (pin "2") (pinfunction "A_2") (pintype "unspecified"))
      (node (ref "PCA-A") (pin "19") (pinfunction "LED12_19") (pintype "unspecified"))
    )
    (net (code "15") (name "Net-(A13-A)") (class "Default")
      (node (ref "A13") (pin "2") (pinfunction "A_2") (pintype "unspecified"))
      (node (ref "PCA-A") (pin "20") (pinfunction "LED13_20") (pintype "unspecified"))
    )
    (net (code "16") (name "Net-(A14-A)") (class "Default")
      (node (ref "A14") (pin "2") (pinfunction "A_2") (pintype "unspecified"))
      (node (ref "PCA-A") (pin "21") (pinfunction "LED14_21") (pintype "unspecified"))
    )
    (net (code "17") (name "Net-(A15-A)") (class "Default")
      (node (ref "A15") (pin "2") (pinfunction "A_2") (pintype "unspecified"))
      (node (ref "PCA-A") (pin "22") (pinfunction "LED15_22") (pintype "unspecified"))
    )
    (net (code "18") (name "Net-(B0-A)") (class "Default")
      (node (ref "B0") (pin "2") (pinfunction "A_2") (pintype "unspecified"))
      (node (ref "PCA-B") (pin "6") (pinfunction "LED0_6") (pintype "unspecified"))
    )
    (net (code "19") (name "Net-(B1-A)") (class "Default")
      (node (ref "B1") (pin "2") (pinfunction "A_2") (pintype "unspecified"))
      (node (ref "PCA-B") (pin "7") (pinfunction "LED1_7") (pintype "unspecified"))
    )
    (net (code "20") (name "Net-(B2-A)") (class "Default")
      (node (ref "B2") (pin "2") (pinfunction "A_2") (pintype "unspecified"))
      (node (ref "PCA-B") (pin "8") (pinfunction "LED2_8") (pintype "unspecified"))
    )
    (net (code "21") (name "Net-(B3-A)") (class "Default")
      (node (ref "B3") (pin "2") (pinfunction "A_2") (pintype "unspecified"))
      (node (ref "PCA-B") (pin "9") (pinfunction "LED3_9") (pintype "unspecified"))
    )
    (net (code "22") (name "Net-(B4-A)") (class "Default")
      (node (ref "B4") (pin "2") (pinfunction "A_2") (pintype "unspecified"))
      (node (ref "PCA-B") (pin "10") (pinfunction "LED4_10") (pintype "unspecified"))
    )
    (net (code "23") (name "Net-(B5-A)") (class "Default")
      (node (ref "B5") (pin "2") (pinfunction "A_2") (pintype "unspecified"))
      (node (ref "PCA-B") (pin "11") (pinfunction "LED5_11") (pintype "unspecified"))
    )
    (net (code "24") (name "Net-(B6-A)") (class "Default")
      (node (ref "B6") (pin "2") (pinfunction "A_2") (pintype "unspecified"))
      (node (ref "PCA-B") (pin "12") (pinfunction "LED6_12") (pintype "unspecified"))
    )
    (net (code "25") (name "Net-(B7-A)") (class "Default")
      (node (ref "B7") (pin "2") (pinfunction "A_2") (pintype "unspecified"))
      (node (ref "PCA-B") (pin "13") (pinfunction "LED7_13") (pintype "unspecified"))
    )
    (net (code "26") (name "Net-(B8-A)") (class "Default")
      (node (ref "B8") (pin "2") (pinfunction "A_2") (pintype "unspecified"))
      (node (ref "PCA-B") (pin "15") (pinfunction "LED8_15") (pintype "unspecified"))
    )
    (net (code "27") (name "Net-(B9-A)") (class "Default")
      (node (ref "B9") (pin "2") (pinfunction "A_2") (pintype "unspecified"))
      (node (ref "PCA-B") (pin "16") (pinfunction "LED9_16") (pintype "unspecified"))
    )
    (net (code "28") (name "Net-(B10-A)") (class "Default")
      (node (ref "B10") (pin "2") (pinfunction "A_2") (pintype "unspecified"))
      (node (ref "PCA-B") (pin "17") (pinfunction "LED10_17") (pintype "unspecified"))
    )
    (net (code "29") (name "Net-(B11-A)") (class "Default")
      (node (ref "B11") (pin "2") (pinfunction "A_2") (pintype "unspecified"))
      (node (ref "PCA-B") (pin "18") (pinfunction "LED11_18") (pintype "unspecified"))
    )
    (net (code "30") (name "Net-(B12-A)") (class "Default")
      (node (ref "B12") (pin "2") (pinfunction "A_2") (pintype "unspecified"))
      (node (ref "PCA-B") (pin "19") (pinfunction "LED12_19") (pintype "unspecified"))
    )
    (net (code "31") (name "Net-(B13-A)") (class "Default")
      (node (ref "B13") (pin "2") (pinfunction "A_2") (pintype "unspecified"))
      (node (ref "PCA-B") (pin "20") (pinfunction "LED13_20") (pintype "unspecified"))
    )
    (net (code "32") (name "Net-(B14-A)") (class "Default")
      (node (ref "B14") (pin "2") (pinfunction "A_2") (pintype "unspecified"))
      (node (ref "PCA-B") (pin "21") (pinfunction "LED14_21") (pintype "unspecified"))
    )
    (net (code "33") (name "Net-(B15-A)") (class "Default")
      (node (ref "B15") (pin "2") (pinfunction "A_2") (pintype "unspecified"))
      (node (ref "PCA-B") (pin "22") (pinfunction "LED15_22") (pintype "unspecified"))
    )
    (net (code "34") (name "Net-(C0-A)") (class "Default")
      (node (ref "C0") (pin "2") (pinfunction "A_2") (pintype "unspecified"))
      (node (ref "PCA-C") (pin "6") (pinfunction "LED0_6") (pintype "unspecified"))
    )
    (net (code "35") (name "Net-(C1-A)") (class "Default")
      (node (ref "C1") (pin "2") (pinfunction "A_2") (pintype "unspecified"))
      (node (ref "PCA-C") (pin "7") (pinfunction "LED1_7") (pintype "unspecified"))
    )
    (net (code "36") (name "Net-(C2-A)") (class "Default")
      (node (ref "C2") (pin "2") (pinfunction "A_2") (pintype "unspecified"))
      (node (ref "PCA-C") (pin "8") (pinfunction "LED2_8") (pintype "unspecified"))
    )
    (net (code "37") (name "Net-(C3-A)") (class "Default")
      (node (ref "C3") (pin "2") (pinfunction "A_2") (pintype "unspecified"))
      (node (ref "PCA-C") (pin "9") (pinfunction "LED3_9") (pintype "unspecified"))
    )
    (net (code "38") (name "Net-(C4-A)") (class "Default")
      (node (ref "C4") (pin "2") (pinfunction "A_2") (pintype "unspecified"))
      (node (ref "PCA-C") (pin "10") (pinfunction "LED4_10") (pintype "unspecified"))
    )
    (net (code "39") (name "Net-(C5-A)") (class "Default")
      (node (ref "C5") (pin "2") (pinfunction "A_2") (pintype "unspecified"))
      (node (ref "PCA-C") (pin "11") (pinfunction "LED5_11") (pintype "unspecified"))
    )
    (net (code "40") (name "Net-(C6-A)") (class "Default")
      (node (ref "C6") (pin "2") (pinfunction "A_2") (pintype "unspecified"))
      (node (ref "PCA-C") (pin "12") (pinfunction "LED6_12") (pintype "unspecified"))
    )
    (net (code "41") (name "Net-(C7-A)") (class "Default")
      (node (ref "C7") (pin "2") (pinfunction "A_2") (pintype "unspecified"))
      (node (ref "PCA-C") (pin "13") (pinfunction "LED7_13") (pintype "unspecified"))
    )
    (net (code "42") (name "Net-(C8-A)") (class "Default")
      (node (ref "C8") (pin "2") (pinfunction "A_2") (pintype "unspecified"))
      (node (ref "PCA-C") (pin "15") (pinfunction "LED8_15") (pintype "unspecified"))
    )
    (net (code "43") (name "Net-(C9-A)") (class "Default")
      (node (ref "C9") (pin "2") (pinfunction "A_2") (pintype "unspecified"))
      (node (ref "PCA-C") (pin "16") (pinfunction "LED9_16") (pintype "unspecified"))
    )
    (net (code "44") (name "Net-(C10-A)") (class "Default")
      (node (ref "C10") (pin "2") (pinfunction "A_2") (pintype "unspecified"))
      (node (ref "PCA-C") (pin "17") (pinfunction "LED10_17") (pintype "unspecified"))
    )
    (net (code "45") (name "Net-(C11-A)") (class "Default")
      (node (ref "C11") (pin "2") (pinfunction "A_2") (pintype "unspecified"))
      (node (ref "PCA-C") (pin "18") (pinfunction "LED11_18") (pintype "unspecified"))
    )
    (net (code "46") (name "Net-(C12-A)") (class "Default")
      (node (ref "C12") (pin "2") (pinfunction "A_2") (pintype "unspecified"))
      (node (ref "PCA-C") (pin "19") (pinfunction "LED12_19") (pintype "unspecified"))
    )
    (net (code "47") (name "Net-(C13-A)") (class "Default")
      (node (ref "C13") (pin "2") (pinfunction "A_2") (pintype "unspecified"))
      (node (ref "PCA-C") (pin "20") (pinfunction "LED13_20") (pintype "unspecified"))
    )
    (net (code "48") (name "Net-(C14-A)") (class "Default")
      (node (ref "C14") (pin "2") (pinfunction "A_2") (pintype "unspecified"))
      (node (ref "PCA-C") (pin "21") (pinfunction "LED14_21") (pintype "unspecified"))
    )
    (net (code "49") (name "Net-(C15-A)") (class "Default")
      (node (ref "C15") (pin "2") (pinfunction "A_2") (pintype "unspecified"))
      (node (ref "PCA-C") (pin "22") (pinfunction "LED15_22") (pintype "unspecified"))
    )
    (net (code "50") (name "Net-(D0-A)") (class "Default")
      (node (ref "D0") (pin "2") (pinfunction "A_2") (pintype "unspecified"))
      (node (ref "PCA-D") (pin "6") (pinfunction "LED0_6") (pintype "unspecified"))
    )
    (net (code "51") (name "Net-(D1-A)") (class "Default")
      (node (ref "D1") (pin "2") (pinfunction "A_2") (pintype "unspecified"))
      (node (ref "PCA-D") (pin "7") (pinfunction "LED1_7") (pintype "unspecified"))
    )
    (net (code "52") (name "Net-(D2-A)") (class "Default")
      (node (ref "D2") (pin "2") (pinfunction "A_2") (pintype "unspecified"))
      (node (ref "PCA-D") (pin "8") (pinfunction "LED2_8") (pintype "unspecified"))
    )
    (net (code "53") (name "Net-(D3-A)") (class "Default")
      (node (ref "D3") (pin "2") (pinfunction "A_2") (pintype "unspecified"))
      (node (ref "PCA-D") (pin "9") (pinfunction "LED3_9") (pintype "unspecified"))
    )
    (net (code "54") (name "Net-(D4-A)") (class "Default")
      (node (ref "D4") (pin "2") (pinfunction "A_2") (pintype "unspecified"))
      (node (ref "PCA-D") (pin "10") (pinfunction "LED4_10") (pintype "unspecified"))
    )
    (net (code "55") (name "Net-(D5-A)") (class "Default")
      (node (ref "D5") (pin "2") (pinfunction "A_2") (pintype "unspecified"))
      (node (ref "PCA-D") (pin "11") (pinfunction "LED5_11") (pintype "unspecified"))
    )
    (net (code "56") (name "Net-(D6-A)") (class "Default")
      (node (ref "D6") (pin "2") (pinfunction "A_2") (pintype "unspecified"))
      (node (ref "PCA-D") (pin "12") (pinfunction "LED6_12") (pintype "unspecified"))
    )
    (net (code "57") (name "Net-(D7-A)") (class "Default")
      (node (ref "D7") (pin "2") (pinfunction "A_2") (pintype "unspecified"))
      (node (ref "PCA-D") (pin "13") (pinfunction "LED7_13") (pintype "unspecified"))
    )
    (net (code "58") (name "Net-(D8-A)") (class "Default")
      (node (ref "D8") (pin "2") (pinfunction "A_2") (pintype "unspecified"))
      (node (ref "PCA-D") (pin "15") (pinfunction "LED8_15") (pintype "unspecified"))
    )
    (net (code "59") (name "Net-(D9-A)") (class "Default")
      (node (ref "D9") (pin "2") (pinfunction "A_2") (pintype "unspecified"))
      (node (ref "PCA-D") (pin "16") (pinfunction "LED9_16") (pintype "unspecified"))
    )
    (net (code "60") (name "Net-(D10-A)") (class "Default")
      (node (ref "D10") (pin "2") (pinfunction "A_2") (pintype "unspecified"))
      (node (ref "PCA-D") (pin "17") (pinfunction "LED10_17") (pintype "unspecified"))
    )
    (net (code "61") (name "Net-(D11-A)") (class "Default")
      (node (ref "D11") (pin "2") (pinfunction "A_2") (pintype "unspecified"))
      (node (ref "PCA-D") (pin "18") (pinfunction "LED11_18") (pintype "unspecified"))
    )
    (net (code "62") (name "Net-(D12-A)") (class "Default")
      (node (ref "D12") (pin "2") (pinfunction "A_2") (pintype "unspecified"))
      (node (ref "PCA-D") (pin "19") (pinfunction "LED12_19") (pintype "unspecified"))
    )
    (net (code "63") (name "Net-(D13-A)") (class "Default")
      (node (ref "D13") (pin "2") (pinfunction "A_2") (pintype "unspecified"))
      (node (ref "PCA-D") (pin "20") (pinfunction "LED13_20") (pintype "unspecified"))
    )
    (net (code "64") (name "Net-(D14-A)") (class "Default")
      (node (ref "D14") (pin "2") (pinfunction "A_2") (pintype "unspecified"))
      (node (ref "PCA-D") (pin "21") (pinfunction "LED14_21") (pintype "unspecified"))
    )
    (net (code "65") (name "Net-(D15-A)") (class "Default")
      (node (ref "D15") (pin "2") (pinfunction "A_2") (pintype "unspecified"))
      (node (ref "PCA-D") (pin "22") (pinfunction "LED15_22") (pintype "unspecified"))
    )
    (net (code "66") (name "Net-(PCA-A-A0)") (class "Default")
      (node (ref "PCA-A") (pin "1") (pinfunction "A0_1") (pintype "unspecified"))
      (node (ref "R12") (pin "2") (pinfunction "2_2") (pintype "input"))
    )
    (net (code "67") (name "Net-(PCA-A-A1)") (class "Default")
      (node (ref "PCA-A") (pin "2") (pinfunction "A1_2") (pintype "unspecified"))
      (node (ref "R13") (pin "2") (pinfunction "2_2") (pintype "input"))
    )
    (net (code "68") (name "Net-(PCA-A-A2)") (class "Default")
      (node (ref "PCA-A") (pin "3") (pinfunction "A2_3") (pintype "unspecified"))
      (node (ref "R14") (pin "2") (pinfunction "2_2") (pintype "input"))
    )
    (net (code "69") (name "Net-(PCA-A-A3)") (class "Default")
      (node (ref "PCA-A") (pin "4") (pinfunction "A3_4") (pintype "unspecified"))
      (node (ref "R15") (pin "2") (pinfunction "2_2") (pintype "input"))
    )
    (net (code "70") (name "Net-(PCA-A-A4)") (class "Default")
      (node (ref "PCA-A") (pin "5") (pinfunction "A4_5") (pintype "unspecified"))
      (node (ref "R16") (pin "2") (pinfunction "2_2") (pintype "input"))
    )
    (net (code "71") (name "Net-(PCA-A-A5)") (class "Default")
      (node (ref "PCA-A") (pin "24") (pinfunction "A5_24") (pintype "unspecified"))
      (node (ref "R11") (pin "1") (pinfunction "1_1") (pintype "input"))
    )
    (net (code "72") (name "Net-(PCA-A-OE#)") (class "Default")
      (node (ref "PCA-A") (pin "23") (pinfunction "OE#_23") (pintype "unspecified"))
      (node (ref "R28") (pin "1") (pinfunction "1_1") (pintype "input"))
    )
    (net (code "73") (name "Net-(PCA-B-A1)") (class "Default")
      (node (ref "PCA-B") (pin "2") (pinfunction "A1_2") (pintype "unspecified"))
      (node (ref "R2") (pin "2") (pinfunction "2_2") (pintype "input"))
    )
    (net (code "74") (name "Net-(PCA-B-A2)") (class "Default")
      (node (ref "PCA-B") (pin "3") (pinfunction "A2_3") (pintype "unspecified"))
      (node (ref "R6") (pin "2") (pinfunction "2_2") (pintype "input"))
    )
    (net (code "75") (name "Net-(PCA-B-A3)") (class "Default")
      (node (ref "PCA-B") (pin "4") (pinfunction "A3_4") (pintype "unspecified"))
      (node (ref "R7") (pin "2") (pinfunction "2_2") (pintype "input"))
    )
    (net (code "76") (name "Net-(PCA-B-A4)") (class "Default")
      (node (ref "PCA-B") (pin "5") (pinfunction "A4_5") (pintype "unspecified"))
      (node (ref "R8") (pin "2") (pinfunction "2_2") (pintype "input"))
    )
    (net (code "77") (name "Net-(PCA-B-A5)") (class "Default")
      (node (ref "PCA-B") (pin "24") (pinfunction "A5_24") (pintype "unspecified"))
      (node (ref "R4") (pin "1") (pinfunction "1_1") (pintype "input"))
    )
    (net (code "78") (name "Net-(PCA-B-OE#)") (class "Default")
      (node (ref "PCA-B") (pin "23") (pinfunction "OE#_23") (pintype "unspecified"))
      (node (ref "R9") (pin "1") (pinfunction "1_1") (pintype "input"))
    )
    (net (code "79") (name "Net-(PCA-C-A0)") (class "Default")
      (node (ref "PCA-C") (pin "1") (pinfunction "A0_1") (pintype "unspecified"))
      (node (ref "R19") (pin "2") (pinfunction "2_2") (pintype "input"))
    )
    (net (code "80") (name "Net-(PCA-C-A2)") (class "Default")
      (node (ref "PCA-C") (pin "3") (pinfunction "A2_3") (pintype "unspecified"))
      (node (ref "R20") (pin "2") (pinfunction "2_2") (pintype "input"))
    )
    (net (code "81") (name "Net-(PCA-C-A3)") (class "Default")
      (node (ref "PCA-C") (pin "4") (pinfunction "A3_4") (pintype "unspecified"))
      (node (ref "R21") (pin "2") (pinfunction "2_2") (pintype "input"))
    )
    (net (code "82") (name "Net-(PCA-C-A4)") (class "Default")
      (node (ref "PCA-C") (pin "5") (pinfunction "A4_5") (pintype "unspecified"))
      (node (ref "R22") (pin "2") (pinfunction "2_2") (pintype "input"))
    )
    (net (code "83") (name "Net-(PCA-C-A5)") (class "Default")
      (node (ref "PCA-C") (pin "24") (pinfunction "A5_24") (pintype "unspecified"))
      (node (ref "R17") (pin "1") (pinfunction "1_1") (pintype "input"))
    )
    (net (code "84") (name "Net-(PCA-C-OE#)") (class "Default")
      (node (ref "PCA-C") (pin "23") (pinfunction "OE#_23") (pintype "unspecified"))
      (node (ref "R18") (pin "1") (pinfunction "1_1") (pintype "input"))
    )
    (net (code "85") (name "Net-(PCA-D-A2)") (class "Default")
      (node (ref "PCA-D") (pin "3") (pinfunction "A2_3") (pintype "unspecified"))
      (node (ref "R25") (pin "2") (pinfunction "2_2") (pintype "input"))
    )
    (net (code "86") (name "Net-(PCA-D-A3)") (class "Default")
      (node (ref "PCA-D") (pin "4") (pinfunction "A3_4") (pintype "unspecified"))
      (node (ref "R26") (pin "2") (pinfunction "2_2") (pintype "input"))
    )
    (net (code "87") (name "Net-(PCA-D-A4)") (class "Default")
      (node (ref "PCA-D") (pin "5") (pinfunction "A4_5") (pintype "unspecified"))
      (node (ref "R27") (pin "2") (pinfunction "2_2") (pintype "input"))
    )
    (net (code "88") (name "Net-(PCA-D-A5)") (class "Default")
      (node (ref "PCA-D") (pin "24") (pinfunction "A5_24") (pintype "unspecified"))
      (node (ref "R29") (pin "1") (pinfunction "1_1") (pintype "input"))
    )
    (net (code "89") (name "Net-(PCA-D-OE#)") (class "Default")
      (node (ref "PCA-D") (pin "23") (pinfunction "OE#_23") (pintype "unspecified"))
      (node (ref "R30") (pin "1") (pinfunction "1_1") (pintype "input"))
    )
    (net (code "90") (name "Net-(U1-3V3)") (class "Default")
      (node (ref "R23") (pin "1") (pinfunction "1_1") (pintype "input"))
      (node (ref "R24") (pin "1") (pinfunction "1_1") (pintype "input"))
      (node (ref "R5") (pin "2") (pinfunction "2_2") (pintype "input"))
      (node (ref "U1") (pin "12") (pinfunction "3V3_12") (pintype "bidirectional"))
      (node (ref "U2") (pin "3") (pinfunction "C_3") (pintype "input"))
    )
    (net (code "91") (name "Net-(U1-5V)") (class "Default")
      (node (ref "U1") (pin "14") (pinfunction "5V_14") (pintype "bidirectional"))
      (node (ref "USB1") (pin "2") (pinfunction "B9_2") (pintype "unspecified"))
      (node (ref "USB1") (pin "5") (pinfunction "A9_5") (pintype "unspecified"))
      (node (ref "USB2") (pin "2") (pinfunction "B9_2") (pintype "unspecified"))
      (node (ref "USB2") (pin "5") (pinfunction "A9_5") (pintype "unspecified"))
    )
    (net (code "92") (name "Net-(U1-PA10_A2_D2)") (class "Default")
      (node (ref "R1") (pin "2") (pinfunction "2_2") (pintype "input"))
      (node (ref "U1") (pin "3") (pinfunction "PA10_A2_D2_3") (pintype "bidirectional"))
    )
    (net (code "93") (name "Net-(U1-PA11_A3_D3)") (class "Default")
      (node (ref "R3") (pin "1") (pinfunction "1_1") (pintype "input"))
      (node (ref "R5") (pin "1") (pinfunction "1_1") (pintype "input"))
      (node (ref "U1") (pin "4") (pinfunction "PA11_A3_D3_4") (pintype "bidirectional"))
    )
    (net (code "94") (name "Net-(U2-B)") (class "Default")
      (node (ref "R1") (pin "1") (pinfunction "1_1") (pintype "input"))
      (node (ref "U2") (pin "1") (pinfunction "B_1") (pintype "input"))
    )
    (net (code "95") (name "SCL") (class "Default")
      (node (ref "PCA-A") (pin "26") (pinfunction "SCL_26") (pintype "unspecified"))
      (node (ref "PCA-B") (pin "26") (pinfunction "SCL_26") (pintype "unspecified"))
      (node (ref "PCA-C") (pin "26") (pinfunction "SCL_26") (pintype "unspecified"))
      (node (ref "PCA-D") (pin "26") (pinfunction "SCL_26") (pintype "unspecified"))
      (node (ref "R23") (pin "2") (pinfunction "2_2") (pintype "input"))
      (node (ref "U1") (pin "5") (pinfunction "PA8_A4_D4_SCL_5") (pintype "bidirectional"))
    )
    (net (code "96") (name "SDA") (class "Default")
      (node (ref "PCA-A") (pin "27") (pinfunction "SDA_27") (pintype "unspecified"))
      (node (ref "PCA-B") (pin "27") (pinfunction "SDA_27") (pintype "unspecified"))
      (node (ref "PCA-C") (pin "27") (pinfunction "SDA_27") (pintype "unspecified"))
      (node (ref "PCA-D") (pin "27") (pinfunction "SDA_27") (pintype "unspecified"))
      (node (ref "R24") (pin "2") (pinfunction "2_2") (pintype "input"))
      (node (ref "U1") (pin "6") (pinfunction "PA9_A5_D5_SDA_6") (pintype "bidirectional"))
    )
    (net (code "97") (name "VDD") (class "Default")
      (node (ref "C16") (pin "1") (pinfunction "1_1") (pintype "input"))
      (node (ref "PCA-A") (pin "28") (pinfunction "VDD_28") (pintype "unspecified"))
      (node (ref "PCA-B") (pin "1") (pinfunction "A0_1") (pintype "unspecified"))
      (node (ref "PCA-B") (pin "28") (pinfunction "VDD_28") (pintype "unspecified"))
      (node (ref "PCA-C") (pin "2") (pinfunction "A1_2") (pintype "unspecified"))
      (node (ref "PCA-C") (pin "28") (pinfunction "VDD_28") (pintype "unspecified"))
      (node (ref "PCA-D") (pin "1") (pinfunction "A0_1") (pintype "unspecified"))
      (node (ref "PCA-D") (pin "2") (pinfunction "A1_2") (pintype "unspecified"))
      (node (ref "PCA-D") (pin "28") (pinfunction "VDD_28") (pintype "unspecified"))
      (node (ref "U2") (pin "2") (pinfunction "E_2") (pintype "input"))
    )
    (net (code "98") (name "unconnected-(U1-PA02_A0_D0-Pad1)") (class "Default")
      (node (ref "U1") (pin "1") (pinfunction "PA02_A0_D0_1") (pintype "bidirectional+no_connect"))
    )
    (net (code "99") (name "unconnected-(U1-PA4_A1_D1-Pad2)") (class "Default")
      (node (ref "U1") (pin "2") (pinfunction "PA4_A1_D1_2") (pintype "bidirectional+no_connect"))
    )
    (net (code "100") (name "unconnected-(U1-PA5_A9_D9_MISO-Pad10)") (class "Default")
      (node (ref "U1") (pin "10") (pinfunction "PA5_A9_D9_MISO_10") (pintype "bidirectional+no_connect"))
    )
    (net (code "101") (name "unconnected-(U1-PA6_A10_D10_MOSI-Pad11)") (class "Default")
      (node (ref "U1") (pin "11") (pinfunction "PA6_A10_D10_MOSI_11") (pintype "bidirectional+no_connect"))
    )
    (net (code "102") (name "unconnected-(U1-PA7_A8_D8_SCK-Pad9)") (class "Default")
      (node (ref "U1") (pin "9") (pinfunction "PA7_A8_D8_SCK_9") (pintype "bidirectional+no_connect"))
    )
    (net (code "103") (name "unconnected-(U1-PB08_A6_D6_TX-Pad7)") (class "Default")
      (node (ref "U1") (pin "7") (pinfunction "PB08_A6_D6_TX_7") (pintype "bidirectional+no_connect"))
    )
    (net (code "104") (name "unconnected-(U1-PB09_A7_D7_RX-Pad8)") (class "Default")
      (node (ref "U1") (pin "8") (pinfunction "PB09_A7_D7_RX_8") (pintype "bidirectional+no_connect"))
    )
    (net (code "105") (name "unconnected-(USB1-A5-Pad3)") (class "Default")
      (node (ref "USB1") (pin "3") (pinfunction "A5_3") (pintype "unspecified"))
    )
    (net (code "106") (name "unconnected-(USB1-B5-Pad4)") (class "Default")
      (node (ref "USB1") (pin "4") (pinfunction "B5_4") (pintype "unspecified"))
    )
    (net (code "107") (name "unconnected-(USB1-Pad0)") (class "Default")
      (node (ref "USB1") (pin "0") (pinfunction "0_0") (pintype "unspecified"))
    )
    (net (code "108") (name "unconnected-(USB1-Pad0)_1") (class "Default")
      (node (ref "USB1") (pin "0") (pinfunction "0_0") (pintype "unspecified"))
    )
    (net (code "109") (name "unconnected-(USB1-Pad0)_2") (class "Default")
      (node (ref "USB1") (pin "0") (pinfunction "0_0") (pintype "unspecified"))
    )
    (net (code "110") (name "unconnected-(USB1-Pad0)_3") (class "Default")
      (node (ref "USB1") (pin "0") (pinfunction "0_0") (pintype "unspecified"))
    )
    (net (code "111") (name "unconnected-(USB2-A5-Pad3)") (class "Default")
      (node (ref "USB2") (pin "3") (pinfunction "A5_3") (pintype "unspecified"))
    )
    (net (code "112") (name "unconnected-(USB2-B5-Pad4)") (class "Default")
      (node (ref "USB2") (pin "4") (pinfunction "B5_4") (pintype "unspecified"))
    )
    (net (code "113") (name "unconnected-(USB2-Pad0)") (class "Default")
      (node (ref "USB2") (pin "0") (pinfunction "0_0") (pintype "unspecified"))
    )
    (net (code "114") (name "unconnected-(USB2-Pad0)_1") (class "Default")
      (node (ref "USB2") (pin "0") (pinfunction "0_0") (pintype "unspecified"))
    )
    (net (code "115") (name "unconnected-(USB2-Pad0)_2") (class "Default")
      (node (ref "USB2") (pin "0") (pinfunction "0_0") (pintype "unspecified"))
    )
    (net (code "116") (name "unconnected-(USB2-Pad0)_3") (class "Default")
      (node (ref "USB2") (pin "0") (pinfunction "0_0") (pintype "unspecified"))
    )
  )
)
